# mqtt_doorbell_v1.net
KiCad netlist of a schematic drawn in EAGLE
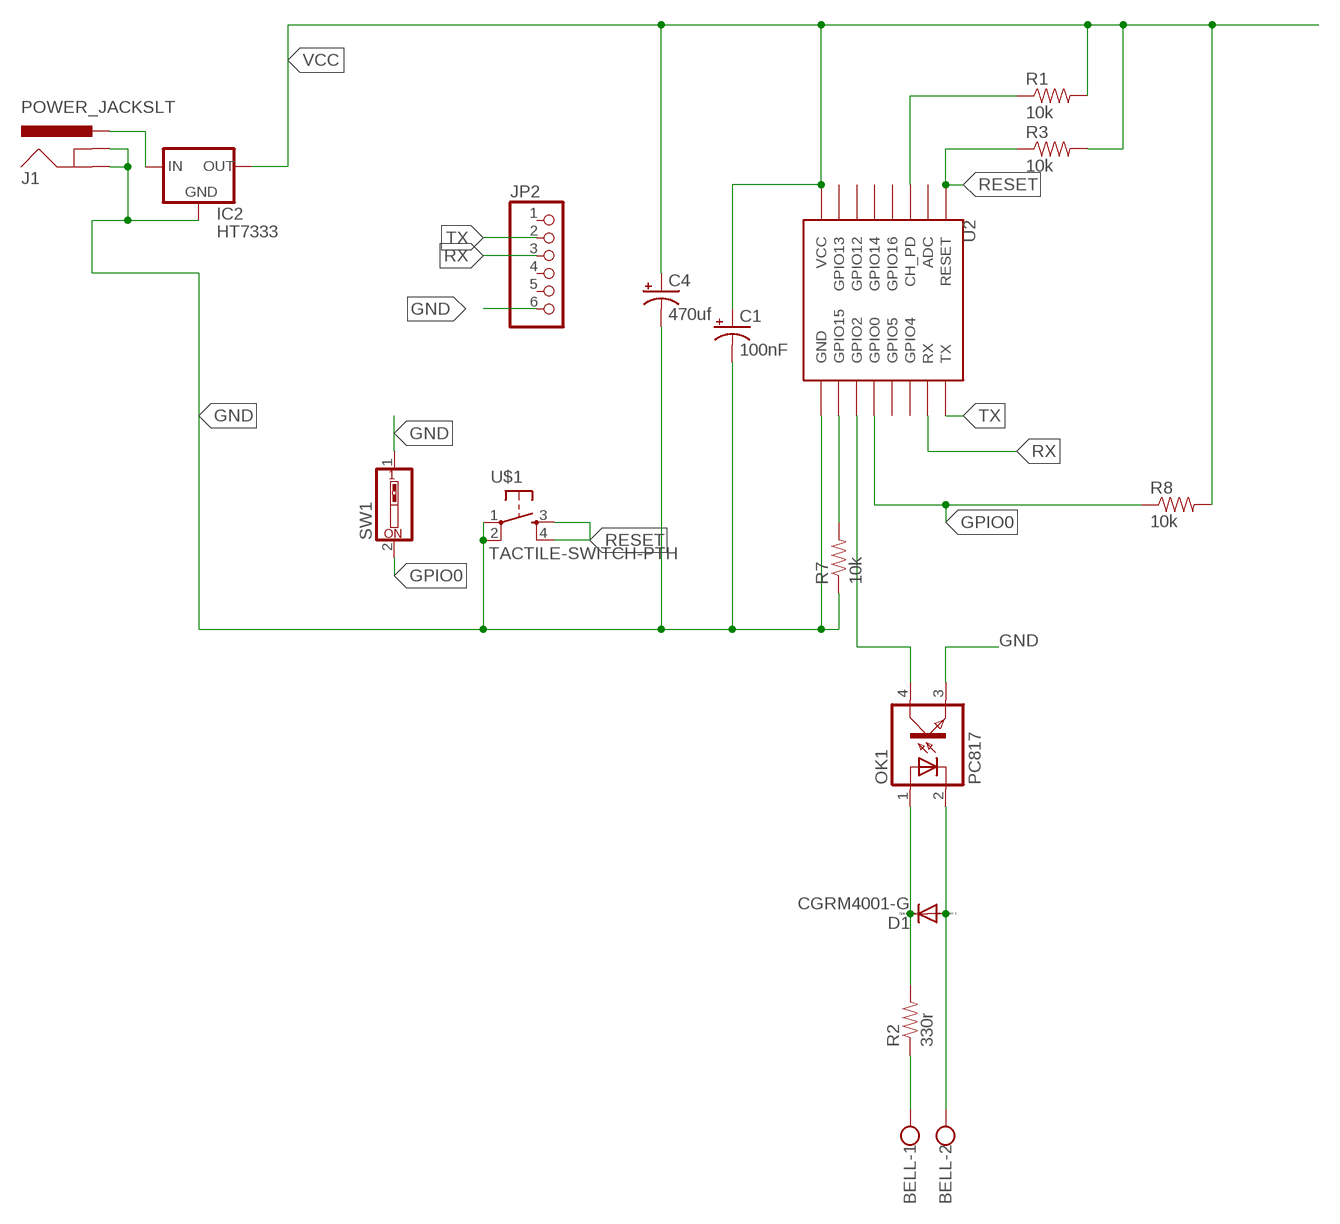
[diagram p0: schematic, sheet 1]

(export (version "E")
  (design (tool "Eeschema 10.0.6"))
  (components
    (comp (ref "BELL")
      (value "W237-102")
      (footprint "eagle-import:W237-102")
      (fields (field (name "MPN") "237-102"))
      (libsource (lib "eagle-import") (part "W237-102"))
    )
    (comp (ref "C1")
      (value "100nF")
      (footprint "eagle-import:EIA3216")
      (libsource (lib "eagle-import") (part "10UF-16V-10%(TANT)"))
    )
    (comp (ref "C4")
      (value "470uf")
      (footprint "eagle-import:PANASONIC_D")
      (libsource (lib "eagle-import") (part "47UF-50V-20%(ELECT)"))
    )
    (comp (ref "D1")
      (value "CGRM4001-G")
      (footprint "eagle-import:SOD-123_MINI-SMA")
      (libsource (lib "eagle-import") (part "CGRM400-G1"))
    )
    (comp (ref "IC2")
      (value "HT7333")
      (footprint "eagle-import:SOT-89")
      (libsource (lib "eagle-import") (part "HT7333"))
    )
    (comp (ref "J1")
      (value "POWER_JACKSLT")
      (footprint "eagle-import:POWER_JACK_SLOT")
      (libsource (lib "eagle-import") (part "POWER_JACKSLT"))
    )
    (comp (ref "JP2")
      (value "PINHD-1X6")
      (footprint "eagle-import:1X06")
      (libsource (lib "eagle-import") (part "PINHD-1X6"))
    )
    (comp (ref "OK1")
      (value "PC817")
      (footprint "eagle-import:DIL04")
      (fields (field (name "MPN") "PC817X4J000F"))
      (libsource (lib "eagle-import") (part "PC817"))
    )
    (comp (ref "R1")
      (value "10k")
      (footprint "eagle-import:1206")
      (libsource (lib "eagle-import") (part "RESISTOR1206"))
    )
    (comp (ref "R2")
      (value "330r")
      (footprint "eagle-import:1206")
      (libsource (lib "eagle-import") (part "RESISTOR1206"))
    )
    (comp (ref "R3")
      (value "10k")
      (footprint "eagle-import:1206")
      (libsource (lib "eagle-import") (part "RESISTOR1206"))
    )
    (comp (ref "R7")
      (value "10k")
      (footprint "eagle-import:1206")
      (libsource (lib "eagle-import") (part "RESISTOR1206"))
    )
    (comp (ref "R8")
      (value "10k")
      (footprint "eagle-import:1206")
      (libsource (lib "eagle-import") (part "RESISTOR1206"))
    )
    (comp (ref "SW1")
      (value "SW_DIP-1")
      (footprint "eagle-import:EDG-01")
      (libsource (lib "eagle-import") (part "SW_DIP-1"))
    )
    (comp (ref "U$1")
      (value "TACTILE-SWITCH-PTH")
      (footprint "eagle-import:TAC-SWITCH-PTH")
      (libsource (lib "eagle-import") (part "TACTILE-SWITCH-PTH"))
    )
    (comp (ref "U2")
      (value "ESP12SMD")
      (footprint "eagle-import:ESP12-SMD")
      (libsource (lib "eagle-import") (part "ESP12SMD"))
    )
  )
  (nets
    (net (code "1") (name "GND") (class "Default")
      (node (ref "C1") (pin "C") (pinfunction "-_C") (pintype "passive"))
      (node (ref "C4") (pin "-") (pinfunction "-_-") (pintype "passive"))
      (node (ref "IC2") (pin "2") (pinfunction "GND_2") (pintype "input"))
      (node (ref "J1") (pin "GND@1") (pinfunction "GNDBREAK_GND@1") (pintype "bidirectional"))
      (node (ref "J1") (pin "GND@2") (pinfunction "GND_GND@2") (pintype "bidirectional"))
      (node (ref "JP2") (pin "6") (pinfunction "6_6") (pintype "passive"))
      (node (ref "OK1") (pin "3") (pinfunction "EMIT_3") (pintype "passive"))
      (node (ref "R7") (pin "1") (pinfunction "1_1") (pintype "passive"))
      (node (ref "SW1") (pin "1") (pinfunction "1_1") (pintype "passive"))
      (node (ref "U$1") (pin "1") (pinfunction "1_1") (pintype "passive"))
      (node (ref "U$1") (pin "2") (pinfunction "2_2") (pintype "passive"))
      (node (ref "U2") (pin "GND") (pinfunction "GND_GND") (pintype "bidirectional"))
    )
    (net (code "2") (name "GPIO0") (class "Default")
      (node (ref "R8") (pin "1") (pinfunction "1_1") (pintype "passive"))
      (node (ref "SW1") (pin "2") (pinfunction "2_2") (pintype "passive"))
      (node (ref "U2") (pin "GPIO0") (pinfunction "GPIO0_GPIO0") (pintype "bidirectional"))
    )
    (net (code "3") (name "Net-(BELLA-KL)") (class "Default")
      (node (ref "BELL") (pin "1") (pinfunction "KL_1") (pintype "passive"))
      (node (ref "R2") (pin "1") (pinfunction "1_1") (pintype "passive"))
    )
    (net (code "4") (name "Net-(BELLB-KL)") (class "Default")
      (node (ref "BELL") (pin "2") (pinfunction "KL_2") (pintype "passive"))
      (node (ref "D1") (pin "A") (pinfunction "A_A") (pintype "passive"))
      (node (ref "OK1") (pin "2") (pinfunction "C_2") (pintype "passive"))
    )
    (net (code "5") (name "Net-(IC2-IN-Pad3)") (class "Default")
      (node (ref "IC2") (pin "3") (pinfunction "IN_3") (pintype "input"))
      (node (ref "IC2") (pin "4") (pinfunction "IN_4") (pintype "input"))
      (node (ref "J1") (pin "PWR") (pinfunction "PWR_PWR") (pintype "bidirectional"))
    )
    (net (code "6") (name "Net-(OK1-A)") (class "Default")
      (node (ref "D1") (pin "C") (pinfunction "C_C") (pintype "passive"))
      (node (ref "OK1") (pin "1") (pinfunction "A_1") (pintype "passive"))
      (node (ref "R2") (pin "2") (pinfunction "2_2") (pintype "passive"))
    )
    (net (code "7") (name "Net-(OK1-COL)") (class "Default")
      (node (ref "OK1") (pin "4") (pinfunction "COL_4") (pintype "passive"))
      (node (ref "U2") (pin "GPIO2") (pinfunction "GPIO2_GPIO2") (pintype "bidirectional"))
    )
    (net (code "8") (name "Net-(R1-Pad1)") (class "Default")
      (node (ref "R1") (pin "1") (pinfunction "1_1") (pintype "passive"))
      (node (ref "U2") (pin "CH_PD") (pinfunction "CH_PD_CH_PD") (pintype "bidirectional"))
    )
    (net (code "9") (name "Net-(R7-Pad2)") (class "Default")
      (node (ref "R7") (pin "2") (pinfunction "2_2") (pintype "passive"))
      (node (ref "U2") (pin "GPIO15") (pinfunction "GPIO15_GPIO15") (pintype "bidirectional"))
    )
    (net (code "10") (name "RESET") (class "Default")
      (node (ref "R3") (pin "1") (pinfunction "1_1") (pintype "passive"))
      (node (ref "U$1") (pin "3") (pinfunction "3_3") (pintype "passive"))
      (node (ref "U$1") (pin "4") (pinfunction "4_4") (pintype "passive"))
      (node (ref "U2") (pin "RESET") (pinfunction "RESET_RESET") (pintype "bidirectional"))
    )
    (net (code "11") (name "RX") (class "Default")
      (node (ref "JP2") (pin "3") (pinfunction "3_3") (pintype "passive"))
      (node (ref "U2") (pin "RXD0") (pinfunction "RX_RXD0") (pintype "bidirectional"))
    )
    (net (code "12") (name "TX") (class "Default")
      (node (ref "JP2") (pin "2") (pinfunction "2_2") (pintype "passive"))
      (node (ref "U2") (pin "TXD0") (pinfunction "TX_TXD0") (pintype "bidirectional"))
    )
    (net (code "13") (name "VCC") (class "Default")
      (node (ref "C1") (pin "A") (pinfunction "+_A") (pintype "passive"))
      (node (ref "C4") (pin "+") (pinfunction "+_+") (pintype "passive"))
      (node (ref "IC2") (pin "1") (pinfunction "OUT_1") (pintype "passive"))
      (node (ref "R1") (pin "2") (pinfunction "2_2") (pintype "passive"))
      (node (ref "R3") (pin "2") (pinfunction "2_2") (pintype "passive"))
      (node (ref "R8") (pin "2") (pinfunction "2_2") (pintype "passive"))
      (node (ref "U2") (pin "VCC") (pinfunction "VCC_VCC") (pintype "bidirectional"))
    )
    (net (code "14") (name "unconnected-(JP2-Pad1)") (class "Default")
      (node (ref "JP2") (pin "1") (pinfunction "1_1") (pintype "passive"))
    )
    (net (code "15") (name "unconnected-(JP2-Pad4)") (class "Default")
      (node (ref "JP2") (pin "4") (pinfunction "4_4") (pintype "passive"))
    )
    (net (code "16") (name "unconnected-(JP2-Pad5)") (class "Default")
      (node (ref "JP2") (pin "5") (pinfunction "5_5") (pintype "passive"))
    )
    (net (code "17") (name "unconnected-(U2-PadADC)") (class "Default")
      (node (ref "U2") (pin "ADC") (pinfunction "ADC_ADC") (pintype "bidirectional"))
    )
    (net (code "18") (name "unconnected-(U2-PadGPIO4)") (class "Default")
      (node (ref "U2") (pin "GPIO4") (pinfunction "GPIO4_GPIO4") (pintype "bidirectional"))
    )
    (net (code "19") (name "unconnected-(U2-PadGPIO5)") (class "Default")
      (node (ref "U2") (pin "GPIO5") (pinfunction "GPIO5_GPIO5") (pintype "bidirectional"))
    )
    (net (code "20") (name "unconnected-(U2-PadGPIO12)") (class "Default")
      (node (ref "U2") (pin "GPIO12") (pinfunction "GPIO12_GPIO12") (pintype "bidirectional"))
    )
    (net (code "21") (name "unconnected-(U2-PadGPIO13)") (class "Default")
      (node (ref "U2") (pin "GPIO13") (pinfunction "GPIO13_GPIO13") (pintype "bidirectional"))
    )
    (net (code "22") (name "unconnected-(U2-PadGPIO14)") (class "Default")
      (node (ref "U2") (pin "GPIO14") (pinfunction "GPIO14_GPIO14") (pintype "bidirectional"))
    )
    (net (code "23") (name "unconnected-(U2-PadGPIO16)") (class "Default")
      (node (ref "U2") (pin "GPIO16") (pinfunction "GPIO16_GPIO16") (pintype "bidirectional"))
    )
  )
)
